# LED.net
KiCad netlist of a schematic drawn in Altium Designer
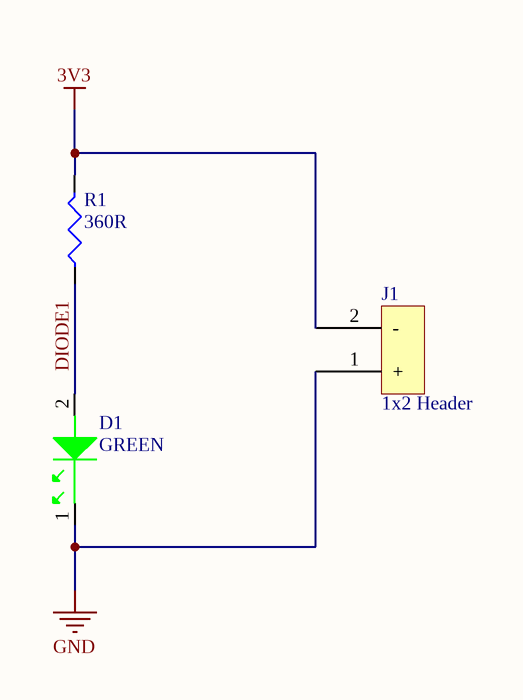
[diagram p0: LED.SchDoc]

(export (version "E")
  (design (tool "Eeschema 10.0.6"))
  (components
    (comp (ref "D1")
      (value "GREEN")
      (footprint "LED0603GREEN")
      (description "LED Uni-Color Green 571nm 2-Pin Chip 0603(1608Metric) T/R")
      (fields
        (field (name "MANUFACTURER") "Visual Communications")
        (field (name "MANUFACTURER PART NUMBER") "LSM0603453V")
      )
      (libsource (lib "LED_Schlib") (part "LSM0603453V"))
    )
    (comp (ref "J1")
      (value "1x2 Header")
      (footprint "HEADER1x2")
      (description "CONN HEADER 2 POS 2.54")
      (fields
        (field (name "MANUFACTURER") "Wurth Electronics")
        (field (name "MANUFACTURER PART NUMBER") "61300211121")
      )
      (libsource (lib "LED_Schlib") (part "61300211121"))
    )
    (comp (ref "R1")
      (value "360R")
      (footprint "R0805")
      (description "Res Thick Film 0805 360 Ohm 1% 0.125W(1/8W) ±100ppm/C Pad SMD T/R")
      (fields
        (field (name "MANUFACTURER") "Yageo")
        (field (name "MANUFACTURER PART NUMBER") "RC0805FR-07360RL")
      )
      (libsource (lib "LED_Schlib") (part "RC0805FR-07360RL"))
    )
  )
  (nets
    (net (code "1") (name "/DIODE1") (class "Default")
      (node (ref "D1") (pin "2") (pinfunction "2_2") (pintype "passive"))
      (node (ref "R1") (pin "1") (pinfunction "1_1") (pintype "passive"))
    )
    (net (code "2") (name "3V3") (class "Default")
      (node (ref "J1") (pin "2") (pinfunction "-_2") (pintype "passive"))
      (node (ref "R1") (pin "2") (pinfunction "2_2") (pintype "passive"))
    )
    (net (code "3") (name "GND") (class "Default")
      (node (ref "D1") (pin "1") (pinfunction "1_1") (pintype "passive"))
      (node (ref "J1") (pin "1") (pinfunction "+_1") (pintype "passive"))
    )
  )
)
